# R2.net
KiCad netlist of a schematic drawn in Altium Designer
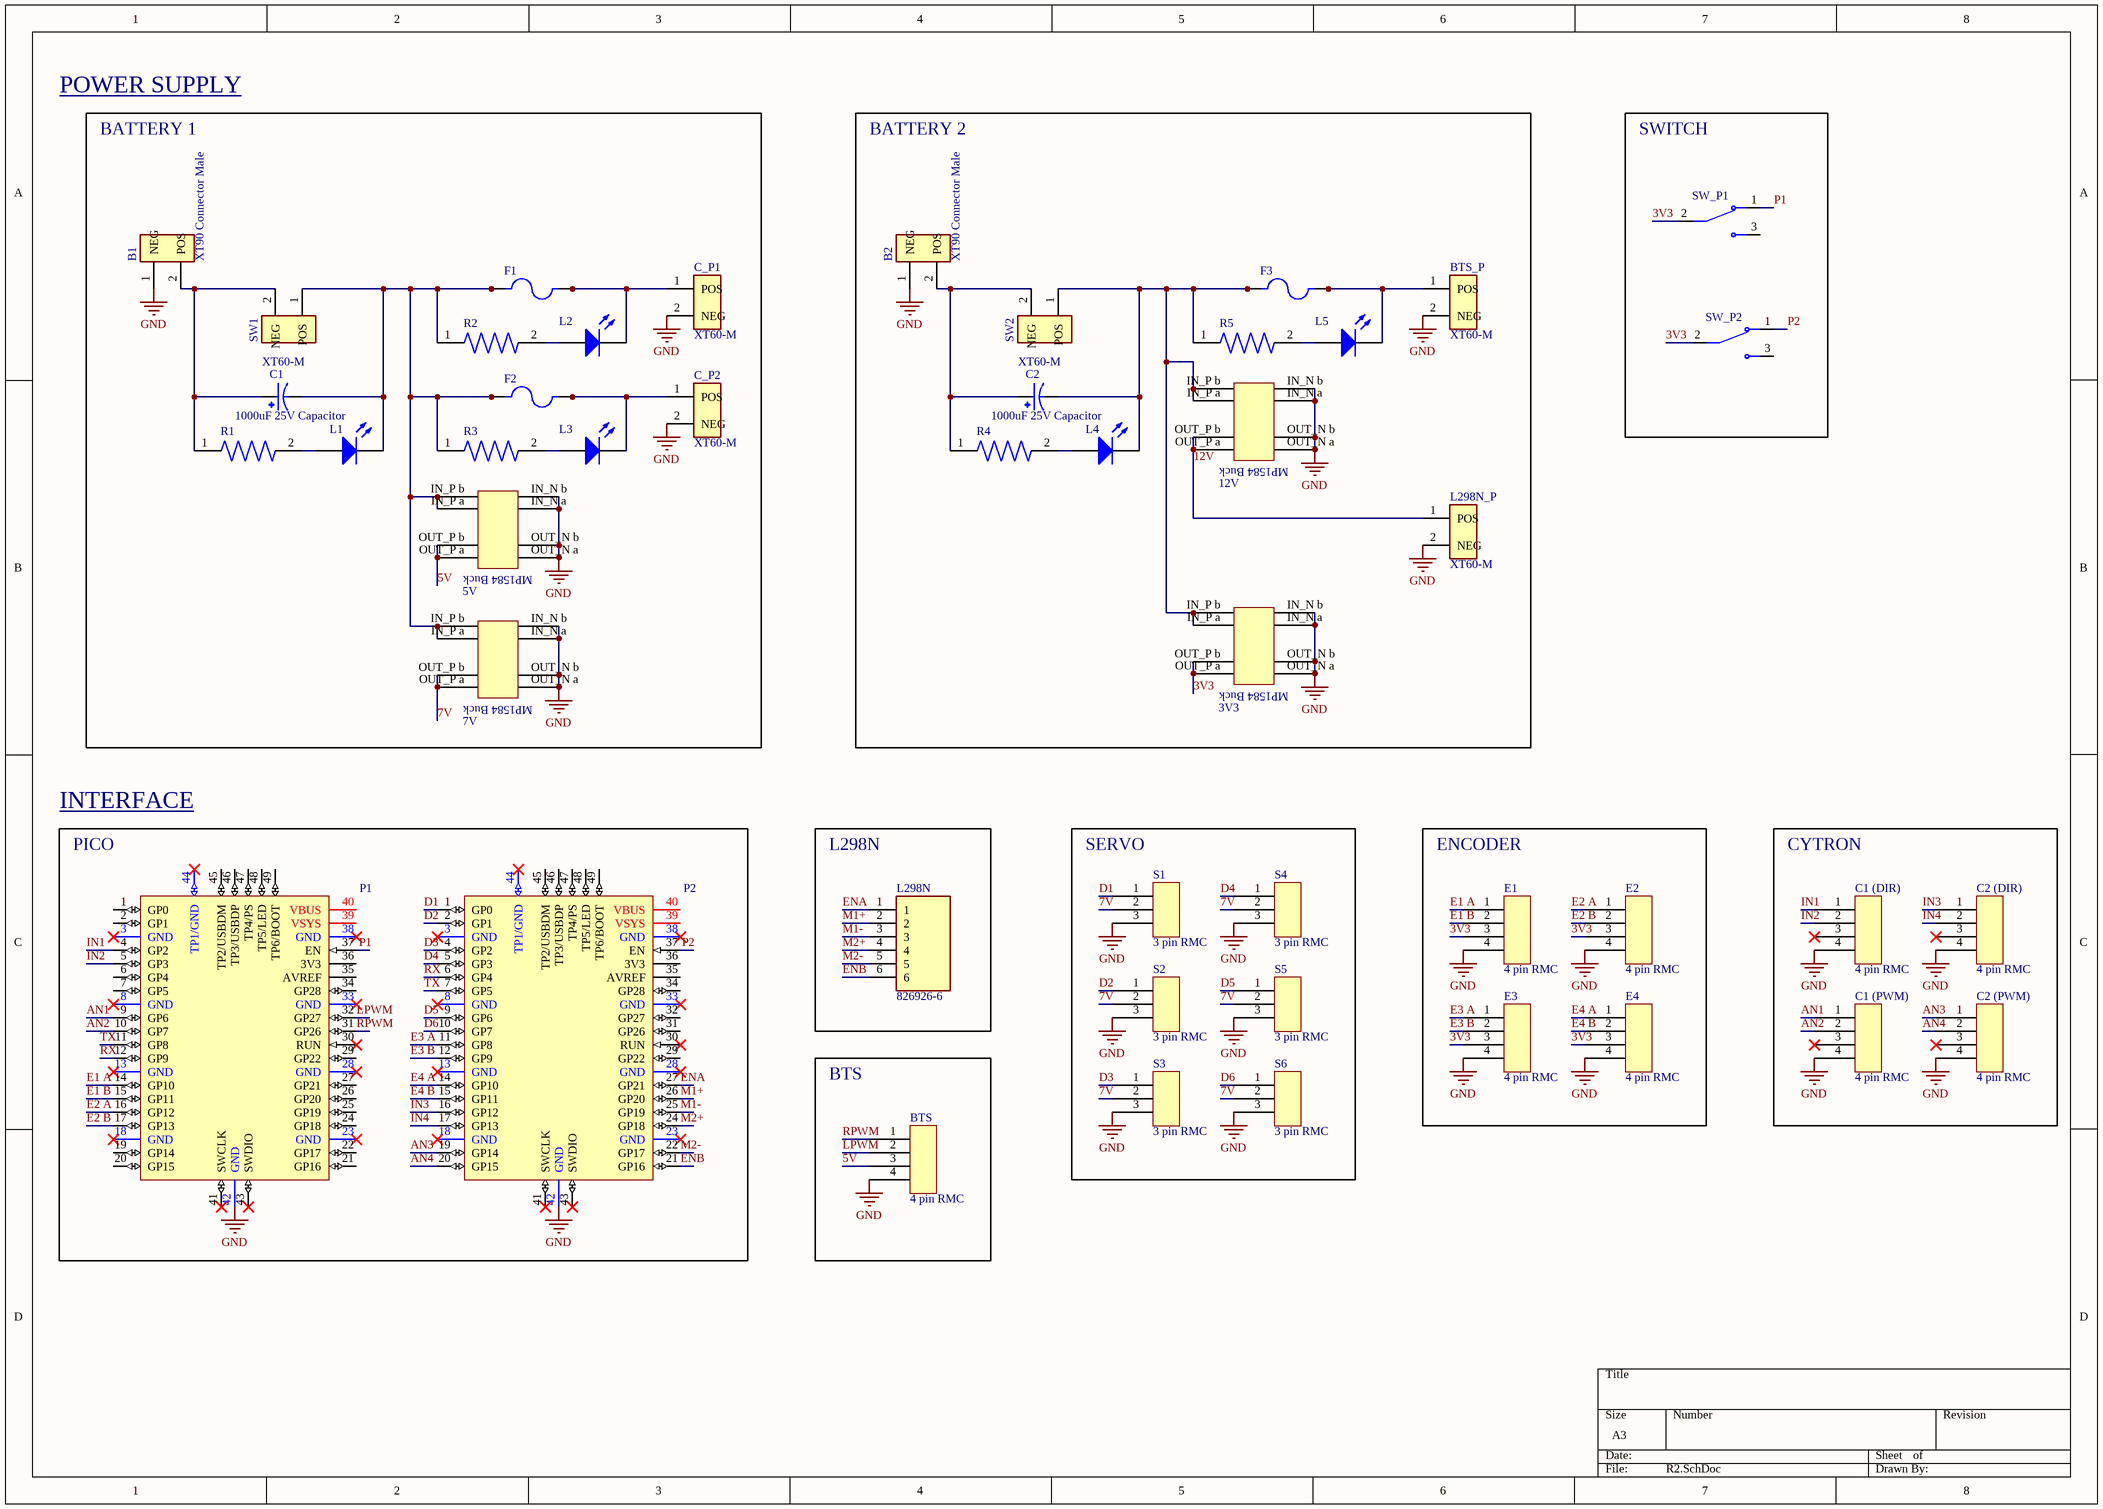
[diagram p0: R2.SchDoc]

(export (version "E")
  (design (tool "Eeschema 10.0.6"))
  (components
    (comp (ref "3V3")
      (value "MP1584 mini buck module")
      (footprint "mp1584 mini buck")
      (libsource (lib "PB R1") (part "MP1584 mini buck module"))
    )
    (comp (ref "5V")
      (value "MP1584 mini buck module")
      (footprint "mp1584 mini buck")
      (libsource (lib "PB R1") (part "MP1584 mini buck module"))
    )
    (comp (ref "7V")
      (value "MP1584 mini buck module")
      (footprint "mp1584 mini buck")
      (libsource (lib "PB R1") (part "MP1584 mini buck module"))
    )
    (comp (ref "12V")
      (value "MP1584 mini buck module")
      (footprint "mp1584 mini buck")
      (libsource (lib "PB R1") (part "MP1584 mini buck module"))
    )
    (comp (ref "B1") (value "XT90-M") (footprint "XT90-M") (libsource (lib "PB R1") (part "XT90-M")))
    (comp (ref "B2") (value "XT90-M") (footprint "XT90-M") (libsource (lib "PB R1") (part "XT90-M")))
    (comp (ref "BTS")
      (value "4 pin RMC")
      (footprint "Header JST 1X04")
      (libsource (lib "R2") (part "4 pin RMC"))
    )
    (comp (ref "BTS_P")
      (value "XT60-M")
      (footprint "XT-60M")
      (description "Plug; DC supply; XT60; male; PIN: 2; for cable; soldered; 30A; 500V")
      (fields (field (name "MF") "AMASS"))
      (libsource (lib "PB R1") (part "XT60-M"))
    )
    (comp (ref "C1")
      (value "1000uF 25V Capacitor")
      (footprint "1000uF 25V Capacitor")
      (description "CAP ALUM 1000UF 20% 25V RADIAL")
      (fields (field (name "MP") "EEUTA1E102LB") (field (name "MF") "Panasonic"))
      (libsource (lib "R2") (part "1000uF 25V Capacitor"))
    )
    (comp (ref "C1 (DIR)")
      (value "4 pin RMC")
      (footprint "Header JST 1X04")
      (libsource (lib "R2") (part "4 pin RMC"))
    )
    (comp (ref "C1 (PWM)")
      (value "4 pin RMC")
      (footprint "Header JST 1X04")
      (libsource (lib "R2") (part "4 pin RMC"))
    )
    (comp (ref "C2")
      (value "1000uF 25V Capacitor")
      (footprint "1000uF 25V Capacitor")
      (description "CAP ALUM 1000UF 20% 25V RADIAL")
      (fields (field (name "MP") "EEUTA1E102LB") (field (name "MF") "Panasonic"))
      (libsource (lib "R2") (part "1000uF 25V Capacitor"))
    )
    (comp (ref "C2 (DIR)")
      (value "4 pin RMC")
      (footprint "Header JST 1X04")
      (libsource (lib "R2") (part "4 pin RMC"))
    )
    (comp (ref "C2 (PWM)")
      (value "4 pin RMC")
      (footprint "Header JST 1X04")
      (libsource (lib "R2") (part "4 pin RMC"))
    )
    (comp (ref "C_P1")
      (value "XT60-M")
      (footprint "XT-60M")
      (description "Plug; DC supply; XT60; male; PIN: 2; for cable; soldered; 30A; 500V")
      (fields (field (name "MF") "AMASS"))
      (libsource (lib "PB R1") (part "XT60-M"))
    )
    (comp (ref "C_P2")
      (value "XT60-M")
      (footprint "XT-60M")
      (description "Plug; DC supply; XT60; male; PIN: 2; for cable; soldered; 30A; 500V")
      (fields (field (name "MF") "AMASS"))
      (libsource (lib "PB R1") (part "XT60-M"))
    )
    (comp (ref "E1")
      (value "4 pin RMC")
      (footprint "Header JST 1X04")
      (libsource (lib "R2") (part "4 pin RMC"))
    )
    (comp (ref "E2")
      (value "4 pin RMC")
      (footprint "Header JST 1X04")
      (libsource (lib "R2") (part "4 pin RMC"))
    )
    (comp (ref "E3")
      (value "4 pin RMC")
      (footprint "Header JST 1X04")
      (libsource (lib "R2") (part "4 pin RMC"))
    )
    (comp (ref "E4")
      (value "4 pin RMC")
      (footprint "Header JST 1X04")
      (libsource (lib "R2") (part "4 pin RMC"))
    )
    (comp (ref "F1")
      (value "3522-2")
      (footprint "FUSE_3522-2")
      (fields (field (name "MF") "{'manufacturer': u'Keystone Electronics'}"))
      (libsource (lib "R2") (part "3522-2"))
    )
    (comp (ref "F2")
      (value "3522-2")
      (footprint "FUSE_3522-2")
      (fields (field (name "MF") "{'manufacturer': u'Keystone Electronics'}"))
      (libsource (lib "R2") (part "3522-2"))
    )
    (comp (ref "F3")
      (value "3522-2")
      (footprint "FUSE_3522-2")
      (fields (field (name "MF") "{'manufacturer': u'Keystone Electronics'}"))
      (libsource (lib "R2") (part "3522-2"))
    )
    (comp (ref "L1")
      (value "151031SS04000 LED")
      (footprint "LED Type 3mm")
      (description "THT LED round mono-color color lens, WL-TMRW, Super Red")
      (fields (field (name "PARTNUMBER") "151031SS04000"))
      (libsource (lib "R2") (part "151031SS04000 LED"))
    )
    (comp (ref "L2")
      (value "151031SS04000 LED")
      (footprint "LED Type 3mm")
      (description "THT LED round mono-color color lens, WL-TMRW, Super Red")
      (fields (field (name "PARTNUMBER") "151031SS04000"))
      (libsource (lib "R2") (part "151031SS04000 LED"))
    )
    (comp (ref "L3")
      (value "151031SS04000 LED")
      (footprint "LED Type 3mm")
      (description "THT LED round mono-color color lens, WL-TMRW, Super Red")
      (fields (field (name "PARTNUMBER") "151031SS04000"))
      (libsource (lib "R2") (part "151031SS04000 LED"))
    )
    (comp (ref "L4")
      (value "151031SS04000 LED")
      (footprint "LED Type 3mm")
      (description "THT LED round mono-color color lens, WL-TMRW, Super Red")
      (fields (field (name "PARTNUMBER") "151031SS04000"))
      (libsource (lib "R2") (part "151031SS04000 LED"))
    )
    (comp (ref "L5")
      (value "151031SS04000 LED")
      (footprint "LED Type 3mm")
      (description "THT LED round mono-color color lens, WL-TMRW, Super Red")
      (fields (field (name "PARTNUMBER") "151031SS04000"))
      (libsource (lib "R2") (part "151031SS04000 LED"))
    )
    (comp (ref "L298N")
      (value "826926-6")
      (footprint "R2:TE_826926-6")
      (description "6P AMPMODU II STIFT LEI")
      (fields (field (name "MF") "TE Connectivity"))
      (libsource (lib "R2") (part "826926-6"))
    )
    (comp (ref "L298N_P")
      (value "XT60-M")
      (footprint "XT-60M")
      (description "Plug; DC supply; XT60; male; PIN: 2; for cable; soldered; 30A; 500V")
      (fields (field (name "MF") "AMASS"))
      (libsource (lib "PB R1") (part "XT60-M"))
    )
    (comp (ref "P1")
      (value "RPI-PICO-MOD")
      (footprint "RPI-PICO-MOD")
      (description "RASPBERRY PI PICO RP2040 BOARD")
      (fields
        (field (name "MANUFACTURER") "Raspberry Pi Foundation")
        (field (name "MANUFACTURER PART NO") "SC0915")
      )
      (libsource (lib "R2") (part "RPI-PICO-MOD"))
    )
    (comp (ref "P2")
      (value "RPI-PICO-MOD")
      (footprint "RPI-PICO-MOD")
      (description "RASPBERRY PI PICO RP2040 BOARD")
      (fields
        (field (name "MANUFACTURER") "Raspberry Pi Foundation")
        (field (name "MANUFACTURER PART NO") "SC0915")
      )
      (libsource (lib "R2") (part "RPI-PICO-MOD"))
    )
    (comp (ref "R1")
      (value "2-1623927-3")
      (footprint "RESAD700W45L350D185")
      (description "Carbon Film Resistors - Through Hole 1K Ohm 5% 1/4W Res Carbon Film")
      (fields (field (name "TOLERANCE") "5%") (field (name "MF") "TE Connectivity"))
      (libsource (lib "R2") (part "2-1623927-3"))
    )
    (comp (ref "R2")
      (value "2-1623927-3")
      (footprint "RESAD700W45L350D185")
      (description "Carbon Film Resistors - Through Hole 1K Ohm 5% 1/4W Res Carbon Film")
      (fields (field (name "TOLERANCE") "5%") (field (name "MF") "TE Connectivity"))
      (libsource (lib "R2") (part "2-1623927-3"))
    )
    (comp (ref "R3")
      (value "2-1623927-3")
      (footprint "RESAD700W45L350D185")
      (description "Carbon Film Resistors - Through Hole 1K Ohm 5% 1/4W Res Carbon Film")
      (fields (field (name "TOLERANCE") "5%") (field (name "MF") "TE Connectivity"))
      (libsource (lib "R2") (part "2-1623927-3"))
    )
    (comp (ref "R4")
      (value "2-1623927-3")
      (footprint "RESAD700W45L350D185")
      (description "Carbon Film Resistors - Through Hole 1K Ohm 5% 1/4W Res Carbon Film")
      (fields (field (name "TOLERANCE") "5%") (field (name "MF") "TE Connectivity"))
      (libsource (lib "R2") (part "2-1623927-3"))
    )
    (comp (ref "R5")
      (value "2-1623927-3")
      (footprint "RESAD700W45L350D185")
      (description "Carbon Film Resistors - Through Hole 1K Ohm 5% 1/4W Res Carbon Film")
      (fields (field (name "TOLERANCE") "5%") (field (name "MF") "TE Connectivity"))
      (libsource (lib "R2") (part "2-1623927-3"))
    )
    (comp (ref "S1")
      (value "3 pin RMC")
      (footprint "Header JST 1X03")
      (libsource (lib "R2") (part "3 pin RMC"))
    )
    (comp (ref "S2")
      (value "3 pin RMC")
      (footprint "Header JST 1X03")
      (libsource (lib "R2") (part "3 pin RMC"))
    )
    (comp (ref "S3")
      (value "3 pin RMC")
      (footprint "Header JST 1X03")
      (libsource (lib "R2") (part "3 pin RMC"))
    )
    (comp (ref "S4")
      (value "3 pin RMC")
      (footprint "Header JST 1X03")
      (libsource (lib "R2") (part "3 pin RMC"))
    )
    (comp (ref "S5")
      (value "3 pin RMC")
      (footprint "Header JST 1X03")
      (libsource (lib "R2") (part "3 pin RMC"))
    )
    (comp (ref "S6")
      (value "3 pin RMC")
      (footprint "Header JST 1X03")
      (libsource (lib "R2") (part "3 pin RMC"))
    )
    (comp (ref "SW1")
      (value "XT60-M")
      (footprint "XT-60M")
      (description "Plug; DC supply; XT60; male; PIN: 2; for cable; soldered; 30A; 500V")
      (fields (field (name "MF") "AMASS"))
      (libsource (lib "") (part "XT60-M_1"))
    )
    (comp (ref "SW2")
      (value "XT60-M")
      (footprint "XT-60M")
      (description "Plug; DC supply; XT60; male; PIN: 2; for cable; soldered; 30A; 500V")
      (fields (field (name "MF") "AMASS"))
      (libsource (lib "") (part "XT60-M_1"))
    )
    (comp (ref "SW_P1")
      (value "500SSP1S2M2QEA")
      (footprint "R2:SW_500SSP1S2M2QEA")
      (description "Slide Switch SPDT Through Hole")
      (libsource (lib "R2") (part "500SSP1S2M2QEA"))
    )
    (comp (ref "SW_P2")
      (value "500SSP1S2M2QEA")
      (footprint "R2:SW_500SSP1S2M2QEA")
      (description "Slide Switch SPDT Through Hole")
      (libsource (lib "R2") (part "500SSP1S2M2QEA"))
    )
  )
  (nets
    (net (code "1") (name "/3V3") (class "Default")
      (node (ref "3V3") (pin "OUT_P_a") (pinfunction "OUT_P_b_OUT_P_a") (pintype "passive"))
      (node (ref "3V3") (pin "OUT_P_b") (pinfunction "OUT_P_b_OUT_P_b") (pintype "passive"))
      (node (ref "E1") (pin "3") (pintype "passive"))
      (node (ref "E2") (pin "3") (pintype "passive"))
      (node (ref "E3") (pin "3") (pintype "passive"))
      (node (ref "E4") (pin "3") (pintype "passive"))
      (node (ref "SW_P1") (pin "2") (pinfunction "COM_2") (pintype "passive"))
      (node (ref "SW_P2") (pin "2") (pinfunction "COM_2") (pintype "passive"))
    )
    (net (code "2") (name "/5V") (class "Default")
      (node (ref "5V") (pin "OUT_P_a") (pinfunction "OUT_P_b_OUT_P_a") (pintype "passive"))
      (node (ref "5V") (pin "OUT_P_b") (pinfunction "OUT_P_b_OUT_P_b") (pintype "passive"))
      (node (ref "BTS") (pin "3") (pintype "passive"))
    )
    (net (code "3") (name "/7V") (class "Default")
      (node (ref "7V") (pin "OUT_P_a") (pinfunction "OUT_P_b_OUT_P_a") (pintype "passive"))
      (node (ref "7V") (pin "OUT_P_b") (pinfunction "OUT_P_b_OUT_P_b") (pintype "passive"))
      (node (ref "S1") (pin "2") (pintype "passive"))
      (node (ref "S2") (pin "2") (pintype "passive"))
      (node (ref "S3") (pin "2") (pintype "passive"))
      (node (ref "S4") (pin "2") (pintype "passive"))
      (node (ref "S5") (pin "2") (pintype "passive"))
      (node (ref "S6") (pin "2") (pintype "passive"))
    )
    (net (code "4") (name "/12V") (class "Default")
      (node (ref "12V") (pin "OUT_P_a") (pinfunction "OUT_P_b_OUT_P_a") (pintype "passive"))
      (node (ref "12V") (pin "OUT_P_b") (pinfunction "OUT_P_b_OUT_P_b") (pintype "passive"))
      (node (ref "L298N_P") (pin "1") (pinfunction "POS_1") (pintype "passive"))
    )
    (net (code "5") (name "/AN1") (class "Default")
      (node (ref "C1 (PWM)") (pin "1") (pintype "passive"))
      (node (ref "P1") (pin "9") (pinfunction "GP6_9") (pintype "bidirectional"))
    )
    (net (code "6") (name "/AN2") (class "Default")
      (node (ref "C1 (PWM)") (pin "2") (pintype "passive"))
      (node (ref "P1") (pin "10") (pinfunction "GP7_10") (pintype "bidirectional"))
    )
    (net (code "7") (name "/AN3") (class "Default")
      (node (ref "C2 (PWM)") (pin "1") (pintype "passive"))
      (node (ref "P2") (pin "19") (pinfunction "GP14_19") (pintype "bidirectional"))
    )
    (net (code "8") (name "/AN4") (class "Default")
      (node (ref "C2 (PWM)") (pin "2") (pintype "passive"))
      (node (ref "P2") (pin "20") (pinfunction "GP15_20") (pintype "bidirectional"))
    )
    (net (code "9") (name "/D1") (class "Default")
      (node (ref "P2") (pin "1") (pinfunction "GP0_1") (pintype "bidirectional"))
      (node (ref "S1") (pin "1") (pintype "passive"))
    )
    (net (code "10") (name "/D2") (class "Default")
      (node (ref "P2") (pin "2") (pinfunction "GP1_2") (pintype "bidirectional"))
      (node (ref "S2") (pin "1") (pintype "passive"))
    )
    (net (code "11") (name "/D3") (class "Default")
      (node (ref "P2") (pin "4") (pinfunction "GP2_4") (pintype "bidirectional"))
      (node (ref "S3") (pin "1") (pintype "passive"))
    )
    (net (code "12") (name "/D4") (class "Default")
      (node (ref "P2") (pin "5") (pinfunction "GP3_5") (pintype "bidirectional"))
      (node (ref "S4") (pin "1") (pintype "passive"))
    )
    (net (code "13") (name "/D5") (class "Default")
      (node (ref "P2") (pin "9") (pinfunction "GP6_9") (pintype "bidirectional"))
      (node (ref "S5") (pin "1") (pintype "passive"))
    )
    (net (code "14") (name "/D6") (class "Default")
      (node (ref "P2") (pin "10") (pinfunction "GP7_10") (pintype "bidirectional"))
      (node (ref "S6") (pin "1") (pintype "passive"))
    )
    (net (code "15") (name "/E1 A") (class "Default")
      (node (ref "E1") (pin "1") (pintype "passive"))
      (node (ref "P1") (pin "14") (pinfunction "GP10_14") (pintype "bidirectional"))
    )
    (net (code "16") (name "/E1 B") (class "Default")
      (node (ref "E1") (pin "2") (pintype "passive"))
      (node (ref "P1") (pin "15") (pinfunction "GP11_15") (pintype "bidirectional"))
    )
    (net (code "17") (name "/E2 A") (class "Default")
      (node (ref "E2") (pin "1") (pintype "passive"))
      (node (ref "P1") (pin "16") (pinfunction "GP12_16") (pintype "bidirectional"))
    )
    (net (code "18") (name "/E2 B") (class "Default")
      (node (ref "E2") (pin "2") (pintype "passive"))
      (node (ref "P1") (pin "17") (pinfunction "GP13_17") (pintype "bidirectional"))
    )
    (net (code "19") (name "/E3 A") (class "Default")
      (node (ref "E3") (pin "1") (pintype "passive"))
      (node (ref "P2") (pin "11") (pinfunction "GP8_11") (pintype "bidirectional"))
    )
    (net (code "20") (name "/E3 B") (class "Default")
      (node (ref "E3") (pin "2") (pintype "passive"))
      (node (ref "P2") (pin "12") (pinfunction "GP9_12") (pintype "bidirectional"))
    )
    (net (code "21") (name "/E4 A") (class "Default")
      (node (ref "E4") (pin "1") (pintype "passive"))
      (node (ref "P2") (pin "14") (pinfunction "GP10_14") (pintype "bidirectional"))
    )
    (net (code "22") (name "/E4 B") (class "Default")
      (node (ref "E4") (pin "2") (pintype "passive"))
      (node (ref "P2") (pin "15") (pinfunction "GP11_15") (pintype "bidirectional"))
    )
    (net (code "23") (name "/ENA") (class "Default")
      (node (ref "L298N") (pin "1") (pinfunction "1_1") (pintype "passive"))
      (node (ref "P2") (pin "27") (pinfunction "GP21_27") (pintype "bidirectional"))
    )
    (net (code "24") (name "/ENB") (class "Default")
      (node (ref "L298N") (pin "6") (pinfunction "6_6") (pintype "passive"))
      (node (ref "P2") (pin "21") (pinfunction "GP16_21") (pintype "bidirectional"))
    )
    (net (code "25") (name "/IN1") (class "Default")
      (node (ref "C1 (DIR)") (pin "1") (pintype "passive"))
      (node (ref "P1") (pin "4") (pinfunction "GP2_4") (pintype "bidirectional"))
    )
    (net (code "26") (name "/IN2") (class "Default")
      (node (ref "C1 (DIR)") (pin "2") (pintype "passive"))
      (node (ref "P1") (pin "5") (pinfunction "GP3_5") (pintype "bidirectional"))
    )
    (net (code "27") (name "/IN3") (class "Default")
      (node (ref "C2 (DIR)") (pin "1") (pintype "passive"))
      (node (ref "P2") (pin "16") (pinfunction "GP12_16") (pintype "bidirectional"))
    )
    (net (code "28") (name "/IN4") (class "Default")
      (node (ref "C2 (DIR)") (pin "2") (pintype "passive"))
      (node (ref "P2") (pin "17") (pinfunction "GP13_17") (pintype "bidirectional"))
    )
    (net (code "29") (name "/LPWM") (class "Default")
      (node (ref "BTS") (pin "2") (pintype "passive"))
      (node (ref "P1") (pin "32") (pinfunction "GP27_32") (pintype "bidirectional"))
    )
    (net (code "30") (name "/M1+") (class "Default")
      (node (ref "L298N") (pin "2") (pinfunction "2_2") (pintype "passive"))
      (node (ref "P2") (pin "26") (pinfunction "GP20_26") (pintype "bidirectional"))
    )
    (net (code "31") (name "/M1-") (class "Default")
      (node (ref "L298N") (pin "3") (pinfunction "3_3") (pintype "passive"))
      (node (ref "P2") (pin "25") (pinfunction "GP19_25") (pintype "bidirectional"))
    )
    (net (code "32") (name "/M2+") (class "Default")
      (node (ref "L298N") (pin "4") (pinfunction "4_4") (pintype "passive"))
      (node (ref "P2") (pin "24") (pinfunction "GP18_24") (pintype "bidirectional"))
    )
    (net (code "33") (name "/M2-") (class "Default")
      (node (ref "L298N") (pin "5") (pinfunction "5_5") (pintype "passive"))
      (node (ref "P2") (pin "22") (pinfunction "GP17_22") (pintype "bidirectional"))
    )
    (net (code "34") (name "/P1") (class "Default")
      (node (ref "P1") (pin "37") (pinfunction "EN_37") (pintype "input"))
      (node (ref "SW_P1") (pin "1") (pinfunction "NC_1") (pintype "passive"))
    )
    (net (code "35") (name "/P2") (class "Default")
      (node (ref "P2") (pin "37") (pinfunction "EN_37") (pintype "input"))
      (node (ref "SW_P2") (pin "1") (pinfunction "NC_1") (pintype "passive"))
    )
    (net (code "36") (name "/RPWM") (class "Default")
      (node (ref "BTS") (pin "1") (pintype "passive"))
      (node (ref "P1") (pin "31") (pinfunction "GP26_31") (pintype "bidirectional"))
    )
    (net (code "37") (name "/RX") (class "Default")
      (node (ref "P1") (pin "12") (pinfunction "GP9_12") (pintype "bidirectional"))
      (node (ref "P2") (pin "6") (pinfunction "GP4_6") (pintype "bidirectional"))
    )
    (net (code "38") (name "/TX") (class "Default")
      (node (ref "P1") (pin "11") (pinfunction "GP8_11") (pintype "bidirectional"))
      (node (ref "P2") (pin "7") (pinfunction "GP5_7") (pintype "bidirectional"))
    )
    (net (code "39") (name "GND") (class "Default")
      (node (ref "12V") (pin "IN_N_a") (pinfunction "IN_N_a_IN_N_a") (pintype "passive"))
      (node (ref "12V") (pin "IN_N_b") (pinfunction "IN_N_b_IN_N_b") (pintype "passive"))
      (node (ref "12V") (pin "OUT_N_a") (pinfunction "OUT_N_a_OUT_N_a") (pintype "passive"))
      (node (ref "12V") (pin "OUT_N_b") (pinfunction "OUT_N_b_OUT_N_b") (pintype "passive"))
      (node (ref "3V3") (pin "IN_N_a") (pinfunction "IN_N_a_IN_N_a") (pintype "passive"))
      (node (ref "3V3") (pin "IN_N_b") (pinfunction "IN_N_b_IN_N_b") (pintype "passive"))
      (node (ref "3V3") (pin "OUT_N_a") (pinfunction "OUT_N_a_OUT_N_a") (pintype "passive"))
      (node (ref "3V3") (pin "OUT_N_b") (pinfunction "OUT_N_b_OUT_N_b") (pintype "passive"))
      (node (ref "5V") (pin "IN_N_a") (pinfunction "IN_N_a_IN_N_a") (pintype "passive"))
      (node (ref "5V") (pin "IN_N_b") (pinfunction "IN_N_b_IN_N_b") (pintype "passive"))
      (node (ref "5V") (pin "OUT_N_a") (pinfunction "OUT_N_a_OUT_N_a") (pintype "passive"))
      (node (ref "5V") (pin "OUT_N_b") (pinfunction "OUT_N_b_OUT_N_b") (pintype "passive"))
      (node (ref "7V") (pin "IN_N_a") (pinfunction "IN_N_a_IN_N_a") (pintype "passive"))
      (node (ref "7V") (pin "IN_N_b") (pinfunction "IN_N_b_IN_N_b") (pintype "passive"))
      (node (ref "7V") (pin "OUT_N_a") (pinfunction "OUT_N_a_OUT_N_a") (pintype "passive"))
      (node (ref "7V") (pin "OUT_N_b") (pinfunction "OUT_N_b_OUT_N_b") (pintype "passive"))
      (node (ref "B1") (pin "1") (pinfunction "NEG_1") (pintype "passive"))
      (node (ref "B2") (pin "1") (pinfunction "NEG_1") (pintype "passive"))
      (node (ref "BTS") (pin "4") (pintype "passive"))
      (node (ref "BTS_P") (pin "2") (pinfunction "NEG_2") (pintype "passive"))
      (node (ref "C1 (DIR)") (pin "4") (pintype "passive"))
      (node (ref "C1 (PWM)") (pin "4") (pintype "passive"))
      (node (ref "C2 (DIR)") (pin "4") (pintype "passive"))
      (node (ref "C2 (PWM)") (pin "4") (pintype "passive"))
      (node (ref "C_P1") (pin "2") (pinfunction "NEG_2") (pintype "passive"))
      (node (ref "C_P2") (pin "2") (pinfunction "NEG_2") (pintype "passive"))
      (node (ref "E1") (pin "4") (pintype "passive"))
      (node (ref "E2") (pin "4") (pintype "passive"))
      (node (ref "E3") (pin "4") (pintype "passive"))
      (node (ref "E4") (pin "4") (pintype "passive"))
      (node (ref "L298N_P") (pin "2") (pinfunction "NEG_2") (pintype "passive"))
      (node (ref "P1") (pin "42") (pinfunction "GND_42") (pintype "power_in"))
      (node (ref "P2") (pin "42") (pinfunction "GND_42") (pintype "power_in"))
      (node (ref "S1") (pin "3") (pintype "passive"))
      (node (ref "S2") (pin "3") (pintype "passive"))
      (node (ref "S3") (pin "3") (pintype "passive"))
      (node (ref "S4") (pin "3") (pintype "passive"))
      (node (ref "S5") (pin "3") (pintype "passive"))
      (node (ref "S6") (pin "3") (pintype "passive"))
    )
    (net (code "40") (name "Net-(B1-POS)") (class "Default")
      (node (ref "B1") (pin "2") (pinfunction "POS_2") (pintype "passive"))
      (node (ref "C1") (pin "P") (pinfunction "P_P") (pintype "passive"))
      (node (ref "R1") (pin "1") (pinfunction "1_1") (pintype "passive"))
      (node (ref "SW1") (pin "2") (pinfunction "NEG_2") (pintype "passive"))
    )
    (net (code "41") (name "Net-(B2-POS)") (class "Default")
      (node (ref "B2") (pin "2") (pinfunction "POS_2") (pintype "passive"))
      (node (ref "C2") (pin "P") (pinfunction "P_P") (pintype "passive"))
      (node (ref "R4") (pin "1") (pinfunction "1_1") (pintype "passive"))
      (node (ref "SW2") (pin "2") (pinfunction "NEG_2") (pintype "passive"))
    )
    (net (code "42") (name "Net-(BTS_P-POS)") (class "Default")
      (node (ref "BTS_P") (pin "1") (pinfunction "POS_1") (pintype "passive"))
      (node (ref "F3") (pin "2A") (pinfunction "2_2A") (pintype "passive"))
      (node (ref "F3") (pin "2B") (pinfunction "2_2B") (pintype "passive"))
      (node (ref "L5") (pin "1") (pinfunction "K_1") (pintype "passive"))
    )
    (net (code "43") (name "Net-(C_P1-POS)") (class "Default")
      (node (ref "C_P1") (pin "1") (pinfunction "POS_1") (pintype "passive"))
      (node (ref "F1") (pin "2A") (pinfunction "2_2A") (pintype "passive"))
      (node (ref "F1") (pin "2B") (pinfunction "2_2B") (pintype "passive"))
      (node (ref "L2") (pin "1") (pinfunction "K_1") (pintype "passive"))
    )
    (net (code "44") (name "Net-(C_P2-POS)") (class "Default")
      (node (ref "C_P2") (pin "1") (pinfunction "POS_1") (pintype "passive"))
      (node (ref "F2") (pin "2A") (pinfunction "2_2A") (pintype "passive"))
      (node (ref "F2") (pin "2B") (pinfunction "2_2B") (pintype "passive"))
      (node (ref "L3") (pin "1") (pinfunction "K_1") (pintype "passive"))
    )
    (net (code "45") (name "Net-(L1-A)") (class "Default")
      (node (ref "L1") (pin "2") (pinfunction "A_2") (pintype "passive"))
      (node (ref "R1") (pin "2") (pinfunction "2_2") (pintype "passive"))
    )
    (net (code "46") (name "Net-(L1-K)") (class "Default")
      (node (ref "5V") (pin "IN_P_a") (pinfunction "IN_P_a_IN_P_a") (pintype "passive"))
      (node (ref "5V") (pin "IN_P_b") (pinfunction "IN_P_b_IN_P_b") (pintype "passive"))
      (node (ref "7V") (pin "IN_P_a") (pinfunction "IN_P_a_IN_P_a") (pintype "passive"))
      (node (ref "7V") (pin "IN_P_b") (pinfunction "IN_P_b_IN_P_b") (pintype "passive"))
      (node (ref "C1") (pin "N") (pinfunction "N_N") (pintype "passive"))
      (node (ref "F1") (pin "1A") (pinfunction "1_1A") (pintype "passive"))
      (node (ref "F1") (pin "1B") (pinfunction "1_1B") (pintype "passive"))
      (node (ref "F2") (pin "1A") (pinfunction "1_1A") (pintype "passive"))
      (node (ref "F2") (pin "1B") (pinfunction "1_1B") (pintype "passive"))
      (node (ref "L1") (pin "1") (pinfunction "K_1") (pintype "passive"))
      (node (ref "R2") (pin "1") (pinfunction "1_1") (pintype "passive"))
      (node (ref "R3") (pin "1") (pinfunction "1_1") (pintype "passive"))
      (node (ref "SW1") (pin "1") (pinfunction "POS_1") (pintype "passive"))
    )
    (net (code "47") (name "Net-(L2-A)") (class "Default")
      (node (ref "L2") (pin "2") (pinfunction "A_2") (pintype "passive"))
      (node (ref "R2") (pin "2") (pinfunction "2_2") (pintype "passive"))
    )
    (net (code "48") (name "Net-(L3-A)") (class "Default")
      (node (ref "L3") (pin "2") (pinfunction "A_2") (pintype "passive"))
      (node (ref "R3") (pin "2") (pinfunction "2_2") (pintype "passive"))
    )
    (net (code "49") (name "Net-(L4-A)") (class "Default")
      (node (ref "L4") (pin "2") (pinfunction "A_2") (pintype "passive"))
      (node (ref "R4") (pin "2") (pinfunction "2_2") (pintype "passive"))
    )
    (net (code "50") (name "Net-(L4-K)") (class "Default")
      (node (ref "12V") (pin "IN_P_a") (pinfunction "IN_P_a_IN_P_a") (pintype "passive"))
      (node (ref "12V") (pin "IN_P_b") (pinfunction "IN_P_b_IN_P_b") (pintype "passive"))
      (node (ref "3V3") (pin "IN_P_a") (pinfunction "IN_P_a_IN_P_a") (pintype "passive"))
      (node (ref "3V3") (pin "IN_P_b") (pinfunction "IN_P_b_IN_P_b") (pintype "passive"))
      (node (ref "C2") (pin "N") (pinfunction "N_N") (pintype "passive"))
      (node (ref "F3") (pin "1A") (pinfunction "1_1A") (pintype "passive"))
      (node (ref "F3") (pin "1B") (pinfunction "1_1B") (pintype "passive"))
      (node (ref "L4") (pin "1") (pinfunction "K_1") (pintype "passive"))
      (node (ref "R5") (pin "1") (pinfunction "1_1") (pintype "passive"))
      (node (ref "SW2") (pin "1") (pinfunction "POS_1") (pintype "passive"))
    )
    (net (code "51") (name "Net-(L5-A)") (class "Default")
      (node (ref "L5") (pin "2") (pinfunction "A_2") (pintype "passive"))
      (node (ref "R5") (pin "2") (pinfunction "2_2") (pintype "passive"))
    )
    (net (code "52") (name "unconnected-(C1 (DIR)-Pad3)") (class "Default")
      (node (ref "C1 (DIR)") (pin "3") (pintype "passive+no_connect"))
    )
    (net (code "53") (name "unconnected-(C1 (PWM)-Pad3)") (class "Default")
      (node (ref "C1 (PWM)") (pin "3") (pintype "passive+no_connect"))
    )
    (net (code "54") (name "unconnected-(C2 (DIR)-Pad3)") (class "Default")
      (node (ref "C2 (DIR)") (pin "3") (pintype "passive+no_connect"))
    )
    (net (code "55") (name "unconnected-(C2 (PWM)-Pad3)") (class "Default")
      (node (ref "C2 (PWM)") (pin "3") (pintype "passive+no_connect"))
    )
    (net (code "56") (name "unconnected-(P1-3V3-Pad36)") (class "Default")
      (node (ref "P1") (pin "36") (pinfunction "3V3_36") (pintype "power_in"))
    )
    (net (code "57") (name "unconnected-(P1-AVREF-Pad35)") (class "Default")
      (node (ref "P1") (pin "35") (pinfunction "AVREF_35") (pintype "power_in"))
    )
    (net (code "58") (name "unconnected-(P1-GND-Pad3)") (class "Default")
      (node (ref "P1") (pin "3") (pinfunction "GND_3") (pintype "power_in+no_connect"))
    )
    (net (code "59") (name "unconnected-(P1-GND-Pad8)") (class "Default")
      (node (ref "P1") (pin "8") (pinfunction "GND_8") (pintype "power_in+no_connect"))
    )
    (net (code "60") (name "unconnected-(P1-GND-Pad13)") (class "Default")
      (node (ref "P1") (pin "13") (pinfunction "GND_13") (pintype "power_in+no_connect"))
    )
    (net (code "61") (name "unconnected-(P1-GND-Pad18)") (class "Default")
      (node (ref "P1") (pin "18") (pinfunction "GND_18") (pintype "power_in+no_connect"))
    )
    (net (code "62") (name "unconnected-(P1-GND-Pad23)") (class "Default")
      (node (ref "P1") (pin "23") (pinfunction "GND_23") (pintype "power_in+no_connect"))
    )
    (net (code "63") (name "unconnected-(P1-GND-Pad28)") (class "Default")
      (node (ref "P1") (pin "28") (pinfunction "GND_28") (pintype "power_in+no_connect"))
    )
    (net (code "64") (name "unconnected-(P1-GND-Pad33)") (class "Default")
      (node (ref "P1") (pin "33") (pinfunction "GND_33") (pintype "power_in+no_connect"))
    )
    (net (code "65") (name "unconnected-(P1-GND-Pad38)") (class "Default")
      (node (ref "P1") (pin "38") (pinfunction "GND_38") (pintype "power_in+no_connect"))
    )
    (net (code "66") (name "unconnected-(P1-GP0-Pad1)") (class "Default")
      (node (ref "P1") (pin "1") (pinfunction "GP0_1") (pintype "bidirectional"))
    )
    (net (code "67") (name "unconnected-(P1-GP1-Pad2)") (class "Default")
      (node (ref "P1") (pin "2") (pinfunction "GP1_2") (pintype "bidirectional"))
    )
    (net (code "68") (name "unconnected-(P1-GP4-Pad6)") (class "Default")
      (node (ref "P1") (pin "6") (pinfunction "GP4_6") (pintype "bidirectional"))
    )
    (net (code "69") (name "unconnected-(P1-GP5-Pad7)") (class "Default")
      (node (ref "P1") (pin "7") (pinfunction "GP5_7") (pintype "bidirectional"))
    )
    (net (code "70") (name "unconnected-(P1-GP14-Pad19)") (class "Default")
      (node (ref "P1") (pin "19") (pinfunction "GP14_19") (pintype "bidirectional"))
    )
    (net (code "71") (name "unconnected-(P1-GP15-Pad20)") (class "Default")
      (node (ref "P1") (pin "20") (pinfunction "GP15_20") (pintype "bidirectional"))
    )
    (net (code "72") (name "unconnected-(P1-GP16-Pad21)") (class "Default")
      (node (ref "P1") (pin "21") (pinfunction "GP16_21") (pintype "bidirectional"))
    )
    (net (code "73") (name "unconnected-(P1-GP17-Pad22)") (class "Default")
      (node (ref "P1") (pin "22") (pinfunction "GP17_22") (pintype "bidirectional"))
    )
    (net (code "74") (name "unconnected-(P1-GP18-Pad24)") (class "Default")
      (node (ref "P1") (pin "24") (pinfunction "GP18_24") (pintype "bidirectional"))
    )
    (net (code "75") (name "unconnected-(P1-GP19-Pad25)") (class "Default")
      (node (ref "P1") (pin "25") (pinfunction "GP19_25") (pintype "bidirectional"))
    )
    (net (code "76") (name "unconnected-(P1-GP20-Pad26)") (class "Default")
      (node (ref "P1") (pin "26") (pinfunction "GP20_26") (pintype "bidirectional"))
    )
    (net (code "77") (name "unconnected-(P1-GP21-Pad27)") (class "Default")
      (node (ref "P1") (pin "27") (pinfunction "GP21_27") (pintype "bidirectional"))
    )
    (net (code "78") (name "unconnected-(P1-GP22-Pad29)") (class "Default")
      (node (ref "P1") (pin "29") (pinfunction "GP22_29") (pintype "bidirectional"))
    )
    (net (code "79") (name "unconnected-(P1-GP28-Pad34)") (class "Default")
      (node (ref "P1") (pin "34") (pinfunction "GP28_34") (pintype "bidirectional"))
    )
    (net (code "80") (name "unconnected-(P1-RUN-Pad30)") (class "Default")
      (node (ref "P1") (pin "30") (pinfunction "RUN_30") (pintype "input+no_connect"))
    )
    (net (code "81") (name "unconnected-(P1-SWCLK-Pad41)") (class "Default")
      (node (ref "P1") (pin "41") (pinfunction "SWCLK_41") (pintype "bidirectional+no_connect"))
    )
    (net (code "82") (name "unconnected-(P1-SWDIO-Pad43)") (class "Default")
      (node (ref "P1") (pin "43") (pinfunction "SWDIO_43") (pintype "bidirectional+no_connect"))
    )
    (net (code "83") (name "unconnected-(P1-TP1{slash}GND-Pad44)") (class "Default")
      (node (ref "P1") (pin "44") (pinfunction "TP1/GND_44") (pintype "bidirectional+no_connect"))
    )
    (net (code "84") (name "unconnected-(P1-TP2{slash}USBDM-Pad45)") (class "Default")
      (node (ref "P1") (pin "45") (pinfunction "TP2/USBDM_45") (pintype "bidirectional"))
    )
    (net (code "85") (name "unconnected-(P1-TP3{slash}USBDP-Pad46)") (class "Default")
      (node (ref "P1") (pin "46") (pinfunction "TP3/USBDP_46") (pintype "bidirectional"))
    )
    (net (code "86") (name "unconnected-(P1-TP4{slash}PS-Pad47)") (class "Default")
      (node (ref "P1") (pin "47") (pinfunction "TP4/PS_47") (pintype "bidirectional"))
    )
    (net (code "87") (name "unconnected-(P1-TP5{slash}LED-Pad48)") (class "Default")
      (node (ref "P1") (pin "48") (pinfunction "TP5/LED_48") (pintype "bidirectional"))
    )
    (net (code "88") (name "unconnected-(P1-TP6{slash}BOOT-Pad49)") (class "Default")
      (node (ref "P1") (pin "49") (pinfunction "TP6/BOOT_49") (pintype "bidirectional"))
    )
    (net (code "89") (name "unconnected-(P1-VBUS-Pad40)") (class "Default")
      (node (ref "P1") (pin "40") (pinfunction "VBUS_40") (pintype "power_in"))
    )
    (net (code "90") (name "unconnected-(P1-VSYS-Pad39)") (class "Default")
      (node (ref "P1") (pin "39") (pinfunction "VSYS_39") (pintype "power_in"))
    )
    (net (code "91") (name "unconnected-(P2-3V3-Pad36)") (class "Default")
      (node (ref "P2") (pin "36") (pinfunction "3V3_36") (pintype "power_in"))
    )
    (net (code "92") (name "unconnected-(P2-AVREF-Pad35)") (class "Default")
      (node (ref "P2") (pin "35") (pinfunction "AVREF_35") (pintype "power_in"))
    )
    (net (code "93") (name "unconnected-(P2-GND-Pad3)") (class "Default")
      (node (ref "P2") (pin "3") (pinfunction "GND_3") (pintype "power_in+no_connect"))
    )
    (net (code "94") (name "unconnected-(P2-GND-Pad8)") (class "Default")
      (node (ref "P2") (pin "8") (pinfunction "GND_8") (pintype "power_in+no_connect"))
    )
    (net (code "95") (name "unconnected-(P2-GND-Pad13)") (class "Default")
      (node (ref "P2") (pin "13") (pinfunction "GND_13") (pintype "power_in+no_connect"))
    )
    (net (code "96") (name "unconnected-(P2-GND-Pad18)") (class "Default")
      (node (ref "P2") (pin "18") (pinfunction "GND_18") (pintype "power_in+no_connect"))
    )
    (net (code "97") (name "unconnected-(P2-GND-Pad23)") (class "Default")
      (node (ref "P2") (pin "23") (pinfunction "GND_23") (pintype "power_in+no_connect"))
    )
    (net (code "98") (name "unconnected-(P2-GND-Pad28)") (class "Default")
      (node (ref "P2") (pin "28") (pinfunction "GND_28") (pintype "power_in+no_connect"))
    )
    (net (code "99") (name "unconnected-(P2-GND-Pad33)") (class "Default")
      (node (ref "P2") (pin "33") (pinfunction "GND_33") (pintype "power_in+no_connect"))
    )
    (net (code "100") (name "unconnected-(P2-GND-Pad38)") (class "Default")
      (node (ref "P2") (pin "38") (pinfunction "GND_38") (pintype "power_in+no_connect"))
    )
    (net (code "101") (name "unconnected-(P2-GP22-Pad29)") (class "Default")
      (node (ref "P2") (pin "29") (pinfunction "GP22_29") (pintype "bidirectional"))
    )
    (net (code "102") (name "unconnected-(P2-GP26-Pad31)") (class "Default")
      (node (ref "P2") (pin "31") (pinfunction "GP26_31") (pintype "bidirectional"))
    )
    (net (code "103") (name "unconnected-(P2-GP27-Pad32)") (class "Default")
      (node (ref "P2") (pin "32") (pinfunction "GP27_32") (pintype "bidirectional"))
    )
    (net (code "104") (name "unconnected-(P2-GP28-Pad34)") (class "Default")
      (node (ref "P2") (pin "34") (pinfunction "GP28_34") (pintype "bidirectional"))
    )
    (net (code "105") (name "unconnected-(P2-RUN-Pad30)") (class "Default")
      (node (ref "P2") (pin "30") (pinfunction "RUN_30") (pintype "input+no_connect"))
    )
    (net (code "106") (name "unconnected-(P2-SWCLK-Pad41)") (class "Default")
      (node (ref "P2") (pin "41") (pinfunction "SWCLK_41") (pintype "bidirectional+no_connect"))
    )
    (net (code "107") (name "unconnected-(P2-SWDIO-Pad43)") (class "Default")
      (node (ref "P2") (pin "43") (pinfunction "SWDIO_43") (pintype "bidirectional+no_connect"))
    )
    (net (code "108") (name "unconnected-(P2-TP1{slash}GND-Pad44)") (class "Default")
      (node (ref "P2") (pin "44") (pinfunction "TP1/GND_44") (pintype "bidirectional+no_connect"))
    )
    (net (code "109") (name "unconnected-(P2-TP2{slash}USBDM-Pad45)") (class "Default")
      (node (ref "P2") (pin "45") (pinfunction "TP2/USBDM_45") (pintype "bidirectional"))
    )
    (net (code "110") (name "unconnected-(P2-TP3{slash}USBDP-Pad46)") (class "Default")
      (node (ref "P2") (pin "46") (pinfunction "TP3/USBDP_46") (pintype "bidirectional"))
    )
    (net (code "111") (name "unconnected-(P2-TP4{slash}PS-Pad47)") (class "Default")
      (node (ref "P2") (pin "47") (pinfunction "TP4/PS_47") (pintype "bidirectional"))
    )
    (net (code "112") (name "unconnected-(P2-TP5{slash}LED-Pad48)") (class "Default")
      (node (ref "P2") (pin "48") (pinfunction "TP5/LED_48") (pintype "bidirectional"))
    )
    (net (code "113") (name "unconnected-(P2-TP6{slash}BOOT-Pad49)") (class "Default")
      (node (ref "P2") (pin "49") (pinfunction "TP6/BOOT_49") (pintype "bidirectional"))
    )
    (net (code "114") (name "unconnected-(P2-VBUS-Pad40)") (class "Default")
      (node (ref "P2") (pin "40") (pinfunction "VBUS_40") (pintype "power_in"))
    )
    (net (code "115") (name "unconnected-(P2-VSYS-Pad39)") (class "Default")
      (node (ref "P2") (pin "39") (pinfunction "VSYS_39") (pintype "power_in"))
    )
    (net (code "116") (name "unconnected-(SW_P1-NO-Pad3)") (class "Default")
      (node (ref "SW_P1") (pin "3") (pinfunction "NO_3") (pintype "passive"))
    )
    (net (code "117") (name "unconnected-(SW_P2-NO-Pad3)") (class "Default")
      (node (ref "SW_P2") (pin "3") (pinfunction "NO_3") (pintype "passive"))
    )
  )
)
